# MCU.net
KiCad netlist of a schematic drawn in Altium Designer
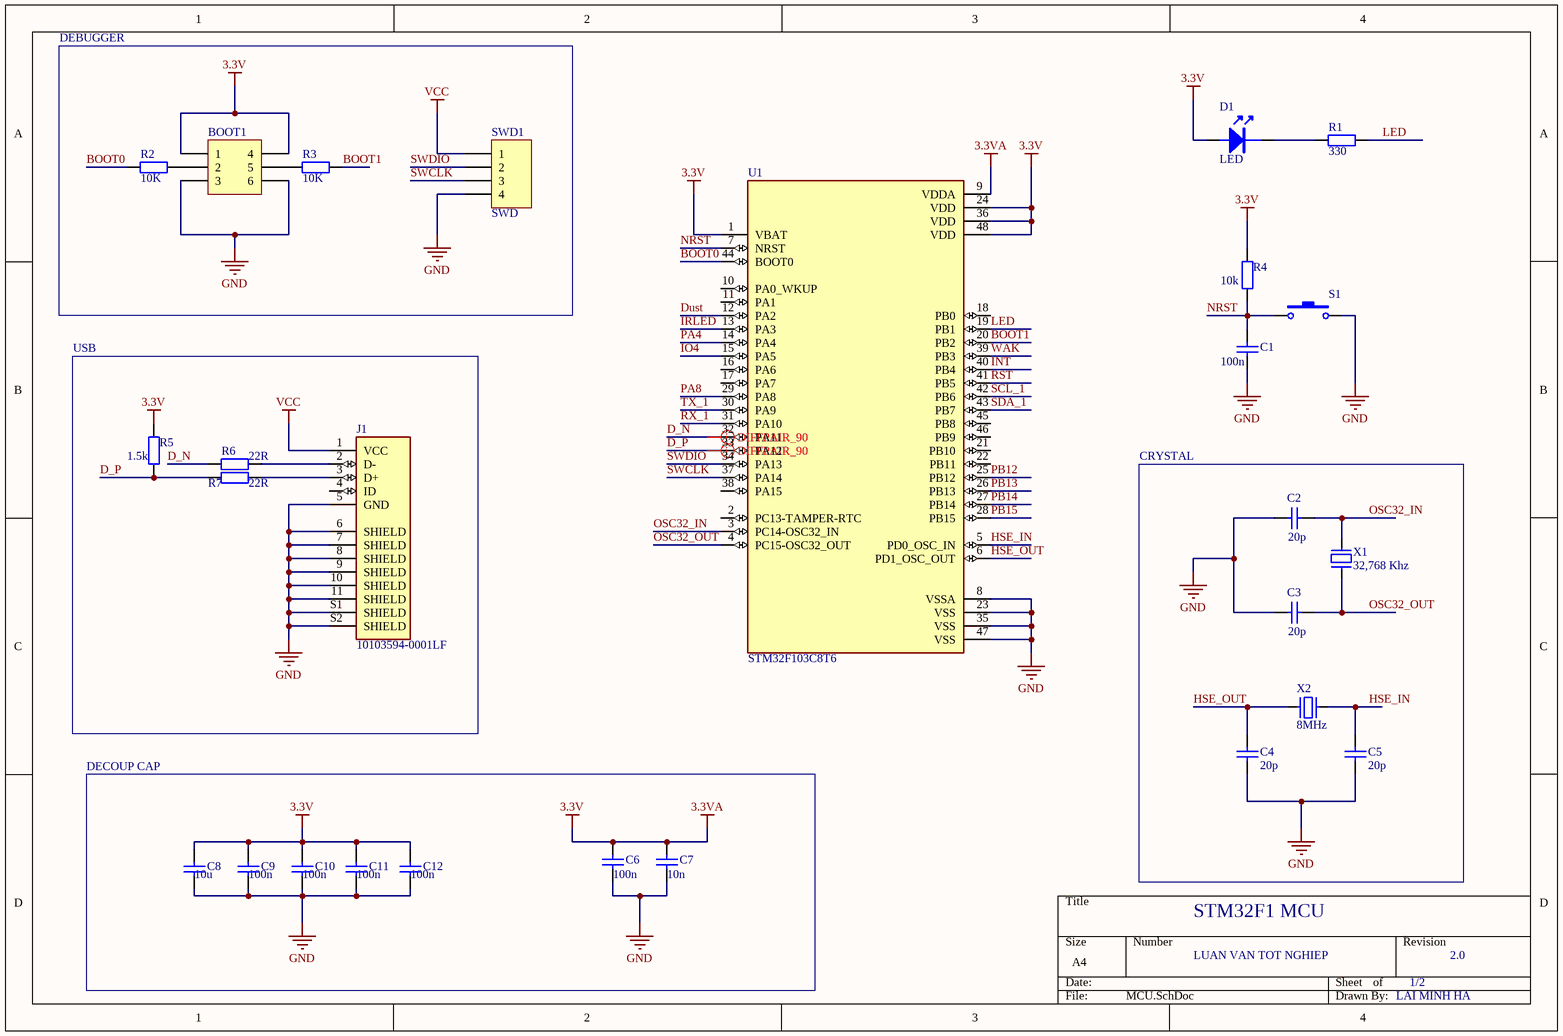
[diagram p0: MCU.SchDoc]

(export (version "E")
  (design (tool "Eeschema 10.0.6"))
  (components
    (comp (ref "BOOT1")
      (value "Header 3X2A")
      (footprint "HDR2X3_CEN")
      (description "Header, 3-Pin, Dual row")
      (fields (field (name "PUBLISHER") "Altium Limited"))
      (libsource (lib "Cty1") (part "Header 3X2A"))
    )
    (comp (ref "C1")
      (value "100n")
      (footprint "C0805")
      (description "Capacitor")
      (fields (field (name "PUBLISHER") "Altium Limited"))
      (libsource (lib "My Library") (part "CapSMD"))
    )
    (comp (ref "C2")
      (value "20p")
      (footprint "C0805")
      (description "Capacitor")
      (fields (field (name "PUBLISHER") "Altium Limited"))
      (libsource (lib "My Library") (part "CapSMD"))
    )
    (comp (ref "C3")
      (value "20p")
      (footprint "C0805")
      (description "Capacitor")
      (fields (field (name "PUBLISHER") "Altium Limited"))
      (libsource (lib "My Library") (part "CapSMD"))
    )
    (comp (ref "C4")
      (value "20p")
      (footprint "C0805")
      (description "Capacitor")
      (fields (field (name "PUBLISHER") "Altium Limited"))
      (libsource (lib "My Library") (part "CapSMD"))
    )
    (comp (ref "C5")
      (value "20p")
      (footprint "C0805")
      (description "Capacitor")
      (fields (field (name "PUBLISHER") "Altium Limited"))
      (libsource (lib "My Library") (part "CapSMD"))
    )
    (comp (ref "C6")
      (value "100n")
      (footprint "C0805")
      (description "Capacitor")
      (fields (field (name "PUBLISHER") "Altium Limited"))
      (libsource (lib "My Library") (part "CapSMD"))
    )
    (comp (ref "C7")
      (value "10n")
      (footprint "C0805")
      (description "Capacitor")
      (fields (field (name "PUBLISHER") "Altium Limited"))
      (libsource (lib "My Library") (part "CapSMD"))
    )
    (comp (ref "C8")
      (value "10u")
      (footprint "C0805")
      (description "Capacitor")
      (fields (field (name "PUBLISHER") "Altium Limited"))
      (libsource (lib "My Library") (part "CapSMD"))
    )
    (comp (ref "C9")
      (value "100n")
      (footprint "C0805")
      (description "Capacitor")
      (fields (field (name "PUBLISHER") "Altium Limited"))
      (libsource (lib "My Library") (part "CapSMD"))
    )
    (comp (ref "C10")
      (value "100n")
      (footprint "C0805")
      (description "Capacitor")
      (fields (field (name "PUBLISHER") "Altium Limited"))
      (libsource (lib "My Library") (part "CapSMD"))
    )
    (comp (ref "C11")
      (value "100n")
      (footprint "C0805")
      (description "Capacitor")
      (fields (field (name "PUBLISHER") "Altium Limited"))
      (libsource (lib "My Library") (part "CapSMD"))
    )
    (comp (ref "C12")
      (value "100n")
      (footprint "C0805")
      (description "Capacitor")
      (fields (field (name "PUBLISHER") "Altium Limited"))
      (libsource (lib "My Library") (part "CapSMD"))
    )
    (comp (ref "D1") (value "LED") (footprint "LED 0805") (libsource (lib "Cty1") (part "LED")))
    (comp (ref "J1")
      (value "10103594-0001LF")
      (footprint "AMPHENOL_10103594-0001LF")
      (description "USB - micro B USB 2.0 Receptacle Connector 5 Position Surface Mount, Right Angle; Through Hole")
      (fields (field (name "MF") "Amphenol ICC (FCI)"))
      (libsource (lib "microusb") (part "10103594-0001LF"))
    )
    (comp (ref "R1")
      (value "330")
      (footprint "DIEN TRO 0805")
      (description "Resistor SMD 0805")
      (fields (field (name "Comment") "R0805") (field (name "PUBLISHER") "Altium Limited"))
      (libsource (lib "My Library") (part "R0805"))
    )
    (comp (ref "R2")
      (value "10K")
      (footprint "DIEN TRO 0805")
      (description "Resistor SMD 0805")
      (fields (field (name "Comment") "R0805") (field (name "PUBLISHER") "Altium Limited"))
      (libsource (lib "My Library") (part "R0805"))
    )
    (comp (ref "R3")
      (value "10K")
      (footprint "DIEN TRO 0805")
      (description "Resistor SMD 0805")
      (fields (field (name "Comment") "R0805") (field (name "PUBLISHER") "Altium Limited"))
      (libsource (lib "My Library") (part "R0805"))
    )
    (comp (ref "R4")
      (value "10k")
      (footprint "DIEN TRO 0805")
      (description "Resistor SMD 0805")
      (fields (field (name "PUBLISHER") "Altium Limited"))
      (libsource (lib "") (part "R0805_1"))
    )
    (comp (ref "R5")
      (value "1.5k")
      (footprint "DIEN TRO 0805")
      (description "Resistor SMD 0805")
      (fields (field (name "PUBLISHER") "Altium Limited"))
      (libsource (lib "") (part "R0805_1"))
    )
    (comp (ref "R6")
      (value "22R")
      (footprint "DIEN TRO 0805")
      (description "Resistor SMD 0805")
      (fields (field (name "PUBLISHER") "Altium Limited"))
      (libsource (lib "My Library") (part "R0805"))
    )
    (comp (ref "R7")
      (value "22R")
      (footprint "DIEN TRO 0805")
      (description "Resistor SMD 0805")
      (fields (field (name "PUBLISHER") "Altium Limited"))
      (libsource (lib "My Library") (part "R0805"))
    )
    (comp (ref "S1")
      (value "SW-SMD")
      (footprint "SW-SMD")
      (description "Switch")
      (fields (field (name "PUBLISHER") "Altium Limited"))
      (libsource (lib "My Library") (part "SW-SMD"))
    )
    (comp (ref "SWD1")
      (value "SWD")
      (footprint "HDR1X4")
      (description "Header, 4-Pin")
      (fields (field (name "PUBLISHER") "Altium Limited"))
      (libsource (lib "Miscellaneous Connectors") (part "Header 4"))
    )
    (comp (ref "U1")
      (value "STM32F103C8T6")
      (footprint "QFP50P900X900X160-48N")
      (description "ARMÂ® CortexÂ®-M3 STM32F1 Microcontroller IC 32-Bit 72MHz 64KB _64K x 8_ FLASH")
      (fields (field (name "MF") "STMicroelectronics"))
      (libsource (lib "STM32F103C8T6") (part "STM32F103C8T6"))
    )
    (comp (ref "X1")
      (value "32,768 Khz")
      (footprint "XT32k")
      (description "Crystal 32,768kHz for timer real")
      (libsource (lib "My Library") (part "XT32k"))
    )
    (comp (ref "X2")
      (value "8MHz")
      (footprint "XT2")
      (description "Crystal For all Crystal 2pin.")
      (libsource (lib "syhaunguyen") (part "XT2"))
    )
  )
  (nets
    (net (code "1") (name "/BOOT0") (class "Default")
      (node (ref "R2") (pin "1") (pinfunction "1_1") (pintype "passive"))
      (node (ref "U1") (pin "44") (pinfunction "BOOT0_44") (pintype "bidirectional"))
    )
    (net (code "2") (name "/BOOT1") (class "Default")
      (node (ref "R3") (pin "2") (pinfunction "2_2") (pintype "passive"))
      (node (ref "U1") (pin "20") (pinfunction "PB2_20") (pintype "bidirectional"))
    )
    (net (code "3") (name "/D_N") (class "Default")
      (node (ref "R6") (pin "1") (pinfunction "1_1") (pintype "passive"))
      (node (ref "U1") (pin "32") (pinfunction "PA11_32") (pintype "bidirectional"))
    )
    (net (code "4") (name "/D_P") (class "Default")
      (node (ref "R5") (pin "2") (pinfunction "2_2") (pintype "passive"))
      (node (ref "R7") (pin "1") (pinfunction "1_1") (pintype "passive"))
      (node (ref "U1") (pin "33") (pinfunction "PA12_33") (pintype "bidirectional"))
    )
    (net (code "5") (name "/Dust") (class "Default")
      (node (ref "U1") (pin "12") (pinfunction "PA2_12") (pintype "bidirectional"))
    )
    (net (code "6") (name "/HSE_IN") (class "Default")
      (node (ref "C5") (pin "2") (pinfunction "2_2") (pintype "passive"))
      (node (ref "U1") (pin "5") (pinfunction "PD0_OSC_IN_5") (pintype "bidirectional"))
      (node (ref "X2") (pin "2") (pinfunction "2_2") (pintype "passive"))
    )
    (net (code "7") (name "/HSE_OUT") (class "Default")
      (node (ref "C4") (pin "2") (pinfunction "2_2") (pintype "passive"))
      (node (ref "U1") (pin "6") (pinfunction "PD1_OSC_OUT_6") (pintype "bidirectional"))
      (node (ref "X2") (pin "1") (pinfunction "1_1") (pintype "passive"))
    )
    (net (code "8") (name "/INT") (class "Default")
      (node (ref "U1") (pin "40") (pinfunction "PB4_40") (pintype "bidirectional"))
    )
    (net (code "9") (name "/IO4") (class "Default")
      (node (ref "U1") (pin "15") (pinfunction "PA5_15") (pintype "bidirectional"))
    )
    (net (code "10") (name "/IRLED") (class "Default")
      (node (ref "U1") (pin "13") (pinfunction "PA3_13") (pintype "bidirectional"))
    )
    (net (code "11") (name "/LED") (class "Default")
      (node (ref "R1") (pin "2") (pinfunction "2_2") (pintype "passive"))
      (node (ref "U1") (pin "19") (pinfunction "PB1_19") (pintype "bidirectional"))
    )
    (net (code "12") (name "/NRST") (class "Default")
      (node (ref "C1") (pin "2") (pinfunction "2_2") (pintype "passive"))
      (node (ref "R4") (pin "2") (pinfunction "2_2") (pintype "passive"))
      (node (ref "S1") (pin "1") (pinfunction "1_1") (pintype "passive"))
      (node (ref "U1") (pin "7") (pinfunction "NRST_7") (pintype "bidirectional"))
    )
    (net (code "13") (name "/OSC32_IN") (class "Default")
      (node (ref "C2") (pin "2") (pinfunction "2_2") (pintype "passive"))
      (node (ref "U1") (pin "3") (pinfunction "PC14-OSC32_IN_3") (pintype "bidirectional"))
      (node (ref "X1") (pin "1") (pinfunction "1_1") (pintype "passive"))
    )
    (net (code "14") (name "/OSC32_OUT") (class "Default")
      (node (ref "C3") (pin "2") (pinfunction "2_2") (pintype "passive"))
      (node (ref "U1") (pin "4") (pinfunction "PC15-OSC32_OUT_4") (pintype "bidirectional"))
      (node (ref "X1") (pin "2") (pinfunction "2_2") (pintype "passive"))
    )
    (net (code "15") (name "/PA4") (class "Default")
      (node (ref "U1") (pin "14") (pinfunction "PA4_14") (pintype "bidirectional"))
    )
    (net (code "16") (name "/PA8") (class "Default")
      (node (ref "U1") (pin "29") (pinfunction "PA8_29") (pintype "bidirectional"))
    )
    (net (code "17") (name "/PB12") (class "Default")
      (node (ref "U1") (pin "25") (pinfunction "PB12_25") (pintype "bidirectional"))
    )
    (net (code "18") (name "/PB13") (class "Default")
      (node (ref "U1") (pin "26") (pinfunction "PB13_26") (pintype "bidirectional"))
    )
    (net (code "19") (name "/PB14") (class "Default")
      (node (ref "U1") (pin "27") (pinfunction "PB14_27") (pintype "bidirectional"))
    )
    (net (code "20") (name "/PB15") (class "Default")
      (node (ref "U1") (pin "28") (pinfunction "PB15_28") (pintype "bidirectional"))
    )
    (net (code "21") (name "/RST") (class "Default")
      (node (ref "U1") (pin "41") (pinfunction "PB5_41") (pintype "bidirectional"))
    )
    (net (code "22") (name "/RX_1") (class "Default")
      (node (ref "U1") (pin "31") (pinfunction "PA10_31") (pintype "bidirectional"))
    )
    (net (code "23") (name "/SCL_1") (class "Default")
      (node (ref "U1") (pin "42") (pinfunction "PB6_42") (pintype "bidirectional"))
    )
    (net (code "24") (name "/SDA_1") (class "Default")
      (node (ref "U1") (pin "43") (pinfunction "PB7_43") (pintype "bidirectional"))
    )
    (net (code "25") (name "/SWCLK") (class "Default")
      (node (ref "SWD1") (pin "3") (pinfunction "3_3") (pintype "passive"))
      (node (ref "U1") (pin "37") (pinfunction "PA14_37") (pintype "bidirectional"))
    )
    (net (code "26") (name "/SWDIO") (class "Default")
      (node (ref "SWD1") (pin "2") (pinfunction "2_2") (pintype "passive"))
      (node (ref "U1") (pin "34") (pinfunction "PA13_34") (pintype "bidirectional"))
    )
    (net (code "27") (name "/TX_1") (class "Default")
      (node (ref "U1") (pin "30") (pinfunction "PA9_30") (pintype "bidirectional"))
    )
    (net (code "28") (name "/WAK") (class "Default")
      (node (ref "U1") (pin "39") (pinfunction "PB3_39") (pintype "bidirectional"))
    )
    (net (code "29") (name "3.3V") (class "Default")
      (node (ref "BOOT1") (pin "1") (pinfunction "1_1") (pintype "passive"))
      (node (ref "BOOT1") (pin "4") (pinfunction "4_4") (pintype "passive"))
      (node (ref "C10") (pin "2") (pinfunction "2_2") (pintype "passive"))
      (node (ref "C11") (pin "2") (pinfunction "2_2") (pintype "passive"))
      (node (ref "C12") (pin "2") (pinfunction "2_2") (pintype "passive"))
      (node (ref "C6") (pin "2") (pinfunction "2_2") (pintype "passive"))
      (node (ref "C7") (pin "2") (pinfunction "2_2") (pintype "passive"))
      (node (ref "C8") (pin "2") (pinfunction "2_2") (pintype "passive"))
      (node (ref "C9") (pin "2") (pinfunction "2_2") (pintype "passive"))
      (node (ref "D1") (pin "1") (pinfunction "1_1") (pintype "passive"))
      (node (ref "R4") (pin "1") (pinfunction "1_1") (pintype "passive"))
      (node (ref "R5") (pin "1") (pinfunction "1_1") (pintype "passive"))
      (node (ref "U1") (pin "1") (pinfunction "VBAT_1") (pintype "power_in"))
      (node (ref "U1") (pin "24") (pinfunction "VDD_24") (pintype "power_in"))
      (node (ref "U1") (pin "36") (pinfunction "VDD_36") (pintype "power_in"))
      (node (ref "U1") (pin "48") (pinfunction "VDD_48") (pintype "power_in"))
      (node (ref "U1") (pin "9") (pinfunction "VDDA_9") (pintype "power_in"))
    )
    (net (code "30") (name "GND") (class "Default")
      (node (ref "BOOT1") (pin "3") (pinfunction "3_3") (pintype "passive"))
      (node (ref "BOOT1") (pin "6") (pinfunction "6_6") (pintype "passive"))
      (node (ref "C1") (pin "1") (pinfunction "1_1") (pintype "passive"))
      (node (ref "C10") (pin "1") (pinfunction "1_1") (pintype "passive"))
      (node (ref "C11") (pin "1") (pinfunction "1_1") (pintype "passive"))
      (node (ref "C12") (pin "1") (pinfunction "1_1") (pintype "passive"))
      (node (ref "C2") (pin "1") (pinfunction "1_1") (pintype "passive"))
      (node (ref "C3") (pin "1") (pinfunction "1_1") (pintype "passive"))
      (node (ref "C4") (pin "1") (pinfunction "1_1") (pintype "passive"))
      (node (ref "C5") (pin "1") (pinfunction "1_1") (pintype "passive"))
      (node (ref "C6") (pin "1") (pinfunction "1_1") (pintype "passive"))
      (node (ref "C7") (pin "1") (pinfunction "1_1") (pintype "passive"))
      (node (ref "C8") (pin "1") (pinfunction "1_1") (pintype "passive"))
      (node (ref "C9") (pin "1") (pinfunction "1_1") (pintype "passive"))
      (node (ref "J1") (pin "10") (pinfunction "SHIELD_10") (pintype "passive"))
      (node (ref "J1") (pin "11") (pinfunction "SHIELD_11") (pintype "passive"))
      (node (ref "J1") (pin "5") (pinfunction "GND_5") (pintype "power_in"))
      (node (ref "J1") (pin "6") (pinfunction "SHIELD_6") (pintype "passive"))
      (node (ref "J1") (pin "7") (pinfunction "SHIELD_7") (pintype "passive"))
      (node (ref "J1") (pin "8") (pinfunction "SHIELD_8") (pintype "passive"))
      (node (ref "J1") (pin "9") (pinfunction "SHIELD_9") (pintype "passive"))
      (node (ref "J1") (pin "S1") (pinfunction "SHIELD_S1") (pintype "passive"))
      (node (ref "J1") (pin "S2") (pinfunction "SHIELD_S2") (pintype "passive"))
      (node (ref "S1") (pin "2") (pinfunction "2_2") (pintype "passive"))
      (node (ref "SWD1") (pin "4") (pinfunction "4_4") (pintype "passive"))
      (node (ref "U1") (pin "23") (pinfunction "VSS_23") (pintype "power_in"))
      (node (ref "U1") (pin "35") (pinfunction "VSS_35") (pintype "power_in"))
      (node (ref "U1") (pin "47") (pinfunction "VSS_47") (pintype "power_in"))
      (node (ref "U1") (pin "8") (pinfunction "VSSA_8") (pintype "power_in"))
    )
    (net (code "31") (name "Net-(BOOT1-Pad2)") (class "Default")
      (node (ref "BOOT1") (pin "2") (pinfunction "2_2") (pintype "passive"))
      (node (ref "R2") (pin "2") (pinfunction "2_2") (pintype "passive"))
    )
    (net (code "32") (name "Net-(BOOT1-Pad5)") (class "Default")
      (node (ref "BOOT1") (pin "5") (pinfunction "5_5") (pintype "passive"))
      (node (ref "R3") (pin "1") (pinfunction "1_1") (pintype "passive"))
    )
    (net (code "33") (name "Net-(D1-Pad2)") (class "Default")
      (node (ref "D1") (pin "2") (pinfunction "2_2") (pintype "passive"))
      (node (ref "R1") (pin "1") (pinfunction "1_1") (pintype "passive"))
    )
    (net (code "34") (name "Net-(J1-D+)") (class "Default")
      (node (ref "J1") (pin "3") (pinfunction "D+_3") (pintype "bidirectional"))
      (node (ref "R7") (pin "2") (pinfunction "2_2") (pintype "passive"))
    )
    (net (code "35") (name "Net-(J1-D-)") (class "Default")
      (node (ref "J1") (pin "2") (pinfunction "D-_2") (pintype "bidirectional"))
      (node (ref "R6") (pin "2") (pinfunction "2_2") (pintype "passive"))
    )
    (net (code "36") (name "VCC") (class "Default")
      (node (ref "J1") (pin "1") (pinfunction "VCC_1") (pintype "power_in"))
      (node (ref "SWD1") (pin "1") (pinfunction "1_1") (pintype "passive"))
    )
    (net (code "37") (name "unconnected-(J1-ID-Pad4)") (class "Default")
      (node (ref "J1") (pin "4") (pinfunction "ID_4") (pintype "bidirectional"))
    )
    (net (code "38") (name "unconnected-(U1-PA0_WKUP-Pad10)") (class "Default")
      (node (ref "U1") (pin "10") (pinfunction "PA0_WKUP_10") (pintype "bidirectional"))
    )
    (net (code "39") (name "unconnected-(U1-PA1-Pad11)") (class "Default")
      (node (ref "U1") (pin "11") (pinfunction "PA1_11") (pintype "bidirectional"))
    )
    (net (code "40") (name "unconnected-(U1-PA6-Pad16)") (class "Default")
      (node (ref "U1") (pin "16") (pinfunction "PA6_16") (pintype "bidirectional"))
    )
    (net (code "41") (name "unconnected-(U1-PA7-Pad17)") (class "Default")
      (node (ref "U1") (pin "17") (pinfunction "PA7_17") (pintype "bidirectional"))
    )
    (net (code "42") (name "unconnected-(U1-PA15-Pad38)") (class "Default")
      (node (ref "U1") (pin "38") (pinfunction "PA15_38") (pintype "bidirectional"))
    )
    (net (code "43") (name "unconnected-(U1-PB0-Pad18)") (class "Default")
      (node (ref "U1") (pin "18") (pinfunction "PB0_18") (pintype "bidirectional"))
    )
    (net (code "44") (name "unconnected-(U1-PB8-Pad45)") (class "Default")
      (node (ref "U1") (pin "45") (pinfunction "PB8_45") (pintype "bidirectional"))
    )
    (net (code "45") (name "unconnected-(U1-PB9-Pad46)") (class "Default")
      (node (ref "U1") (pin "46") (pinfunction "PB9_46") (pintype "bidirectional"))
    )
    (net (code "46") (name "unconnected-(U1-PB10-Pad21)") (class "Default")
      (node (ref "U1") (pin "21") (pinfunction "PB10_21") (pintype "bidirectional"))
    )
    (net (code "47") (name "unconnected-(U1-PB11-Pad22)") (class "Default")
      (node (ref "U1") (pin "22") (pinfunction "PB11_22") (pintype "bidirectional"))
    )
    (net (code "48") (name "unconnected-(U1-PC13-TAMPER-RTC-Pad2)") (class "Default")
      (node (ref "U1") (pin "2") (pinfunction "PC13-TAMPER-RTC_2") (pintype "bidirectional"))
    )
  )
)
